# LAB_20200315_0_VoltageDivider.net
KiCad netlist of a schematic drawn in EAGLE
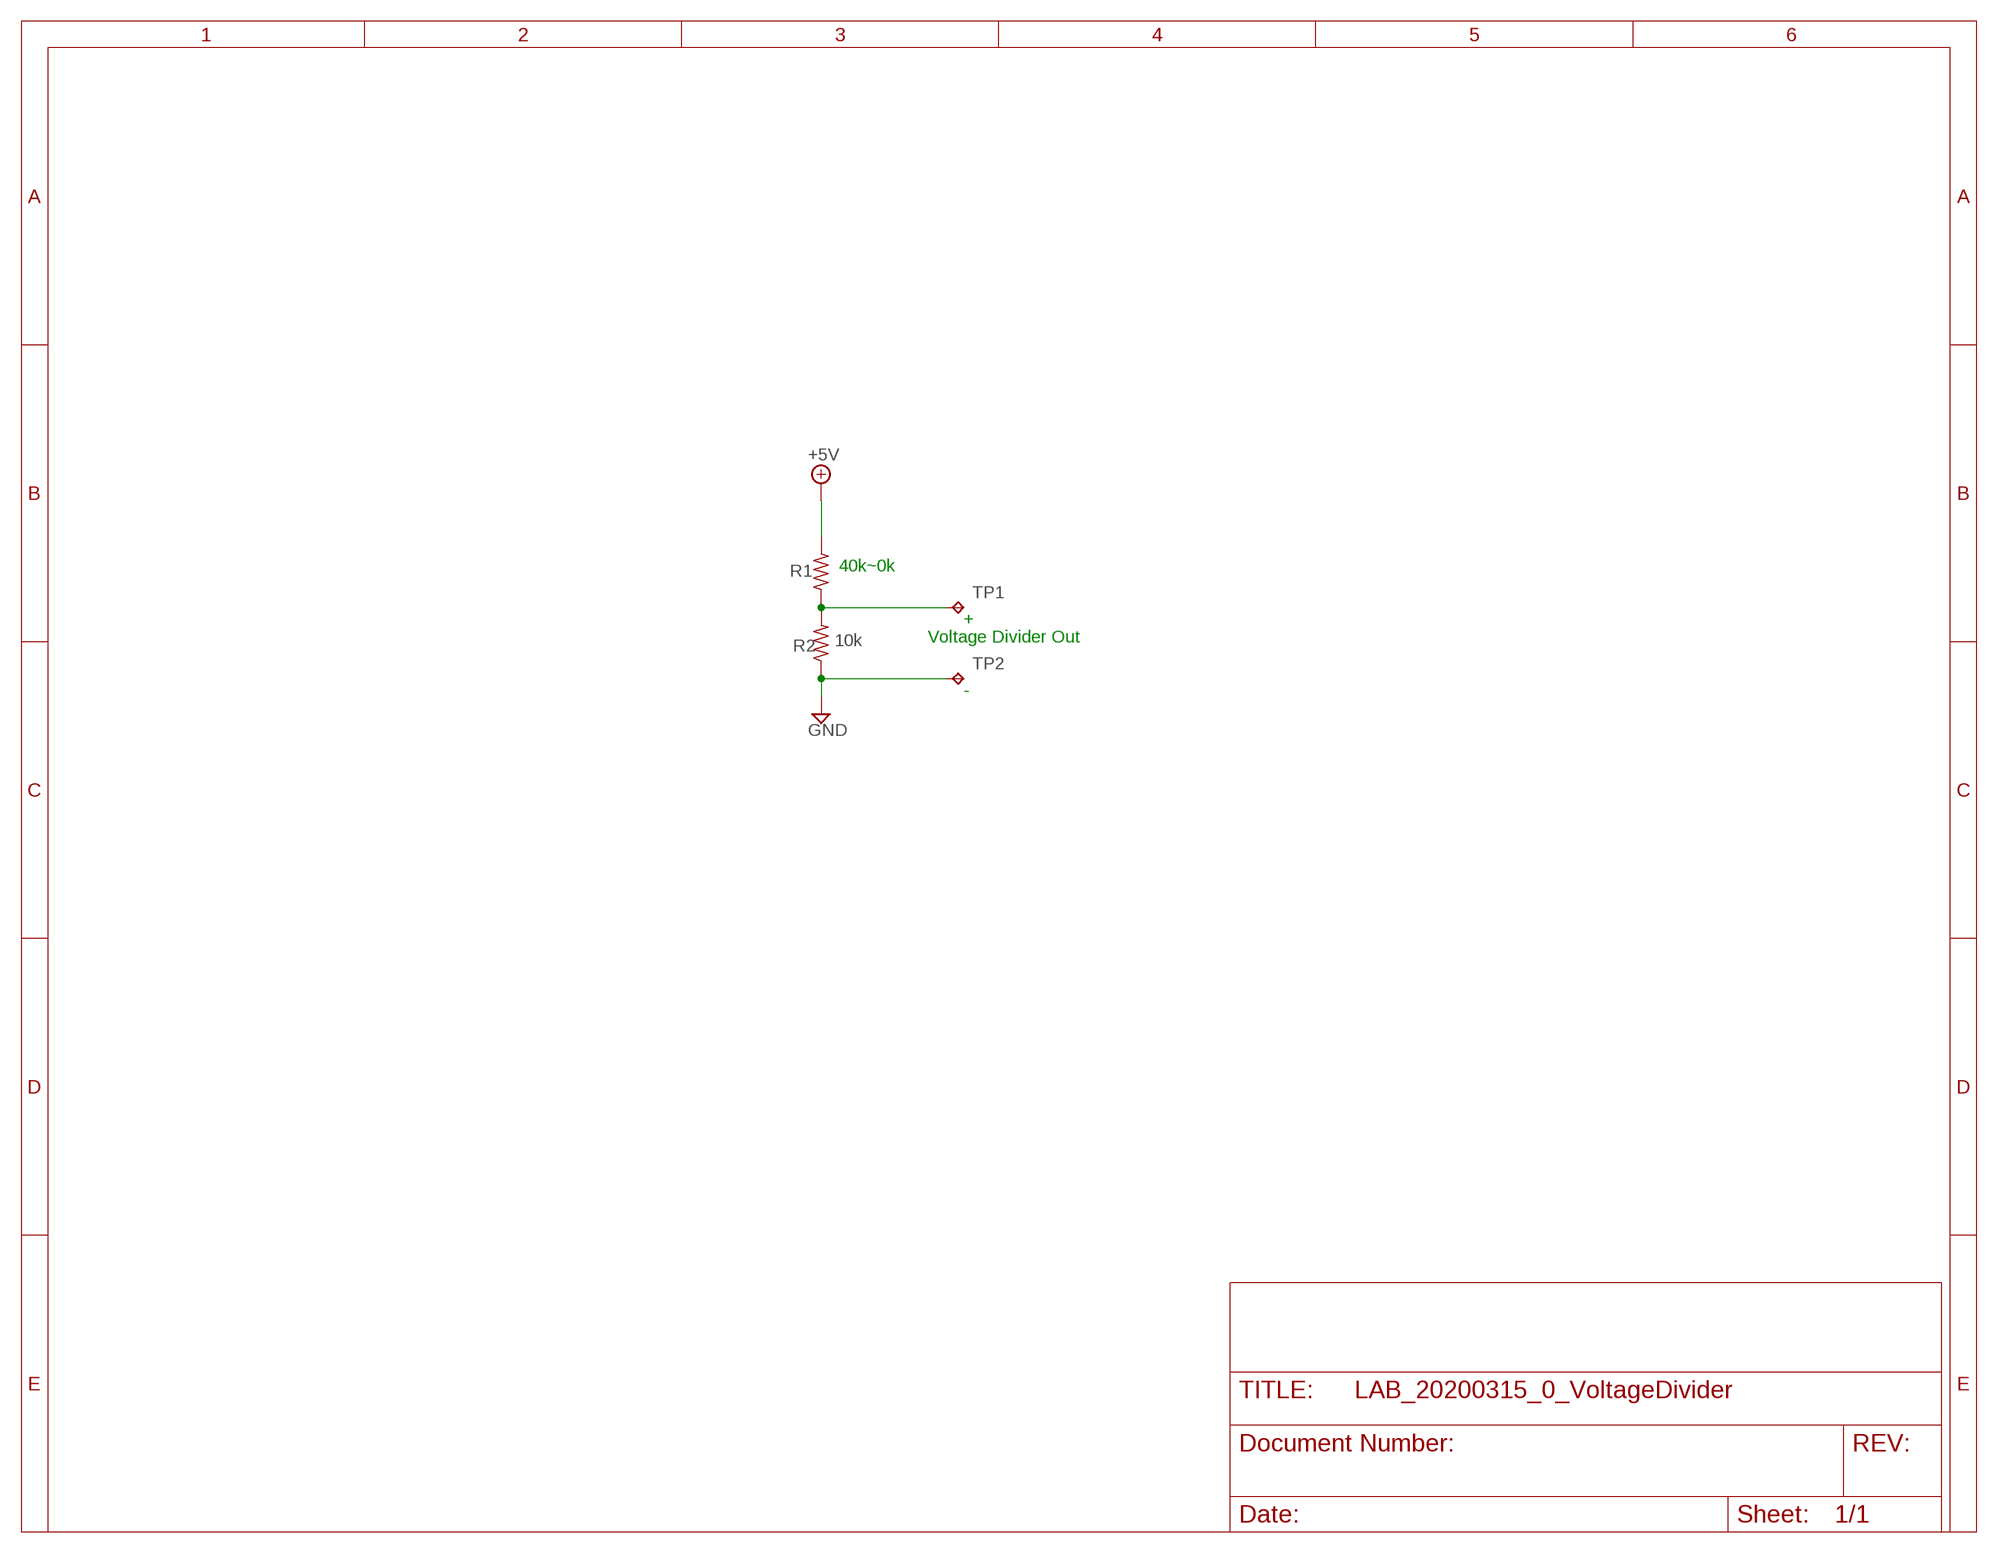
[diagram p0: schematic, sheet 1]

(export (version "E")
  (design (tool "Eeschema 10.0.6"))
  (components
    (comp (ref "R1")
      (value "R-US_0207/12")
      (footprint "eagle-import:0207_12")
      (libsource (lib "eagle-import") (part "R-US_0207/12"))
    )
    (comp (ref "R2")
      (value "10k")
      (footprint "eagle-import:0207_12")
      (libsource (lib "eagle-import") (part "R-US_0207/12"))
    )
    (comp (ref "TP1")
      (value "TPB1,27")
      (footprint "eagle-import:B1,27")
      (libsource (lib "eagle-import") (part "TPB1,27"))
    )
    (comp (ref "TP2")
      (value "TPB1,27")
      (footprint "eagle-import:B1,27")
      (libsource (lib "eagle-import") (part "TPB1,27"))
    )
  )
  (nets
    (net (code "1") (name "+5V") (class "Default")
      (node (ref "R1") (pin "2") (pinfunction "2_2") (pintype "passive"))
    )
    (net (code "2") (name "GND") (class "Default")
      (node (ref "R2") (pin "1") (pinfunction "1_1") (pintype "passive"))
      (node (ref "TP2") (pin "TP") (pinfunction "TP_TP") (pintype "input"))
    )
    (net (code "3") (name "Net-(R1-Pad1)") (class "Default")
      (node (ref "R1") (pin "1") (pinfunction "1_1") (pintype "passive"))
      (node (ref "R2") (pin "2") (pinfunction "2_2") (pintype "passive"))
      (node (ref "TP1") (pin "TP") (pinfunction "TP_TP") (pintype "input"))
    )
  )
)
